# Wireless_Temp_Sensor.net
KiCad netlist of a schematic drawn in EAGLE
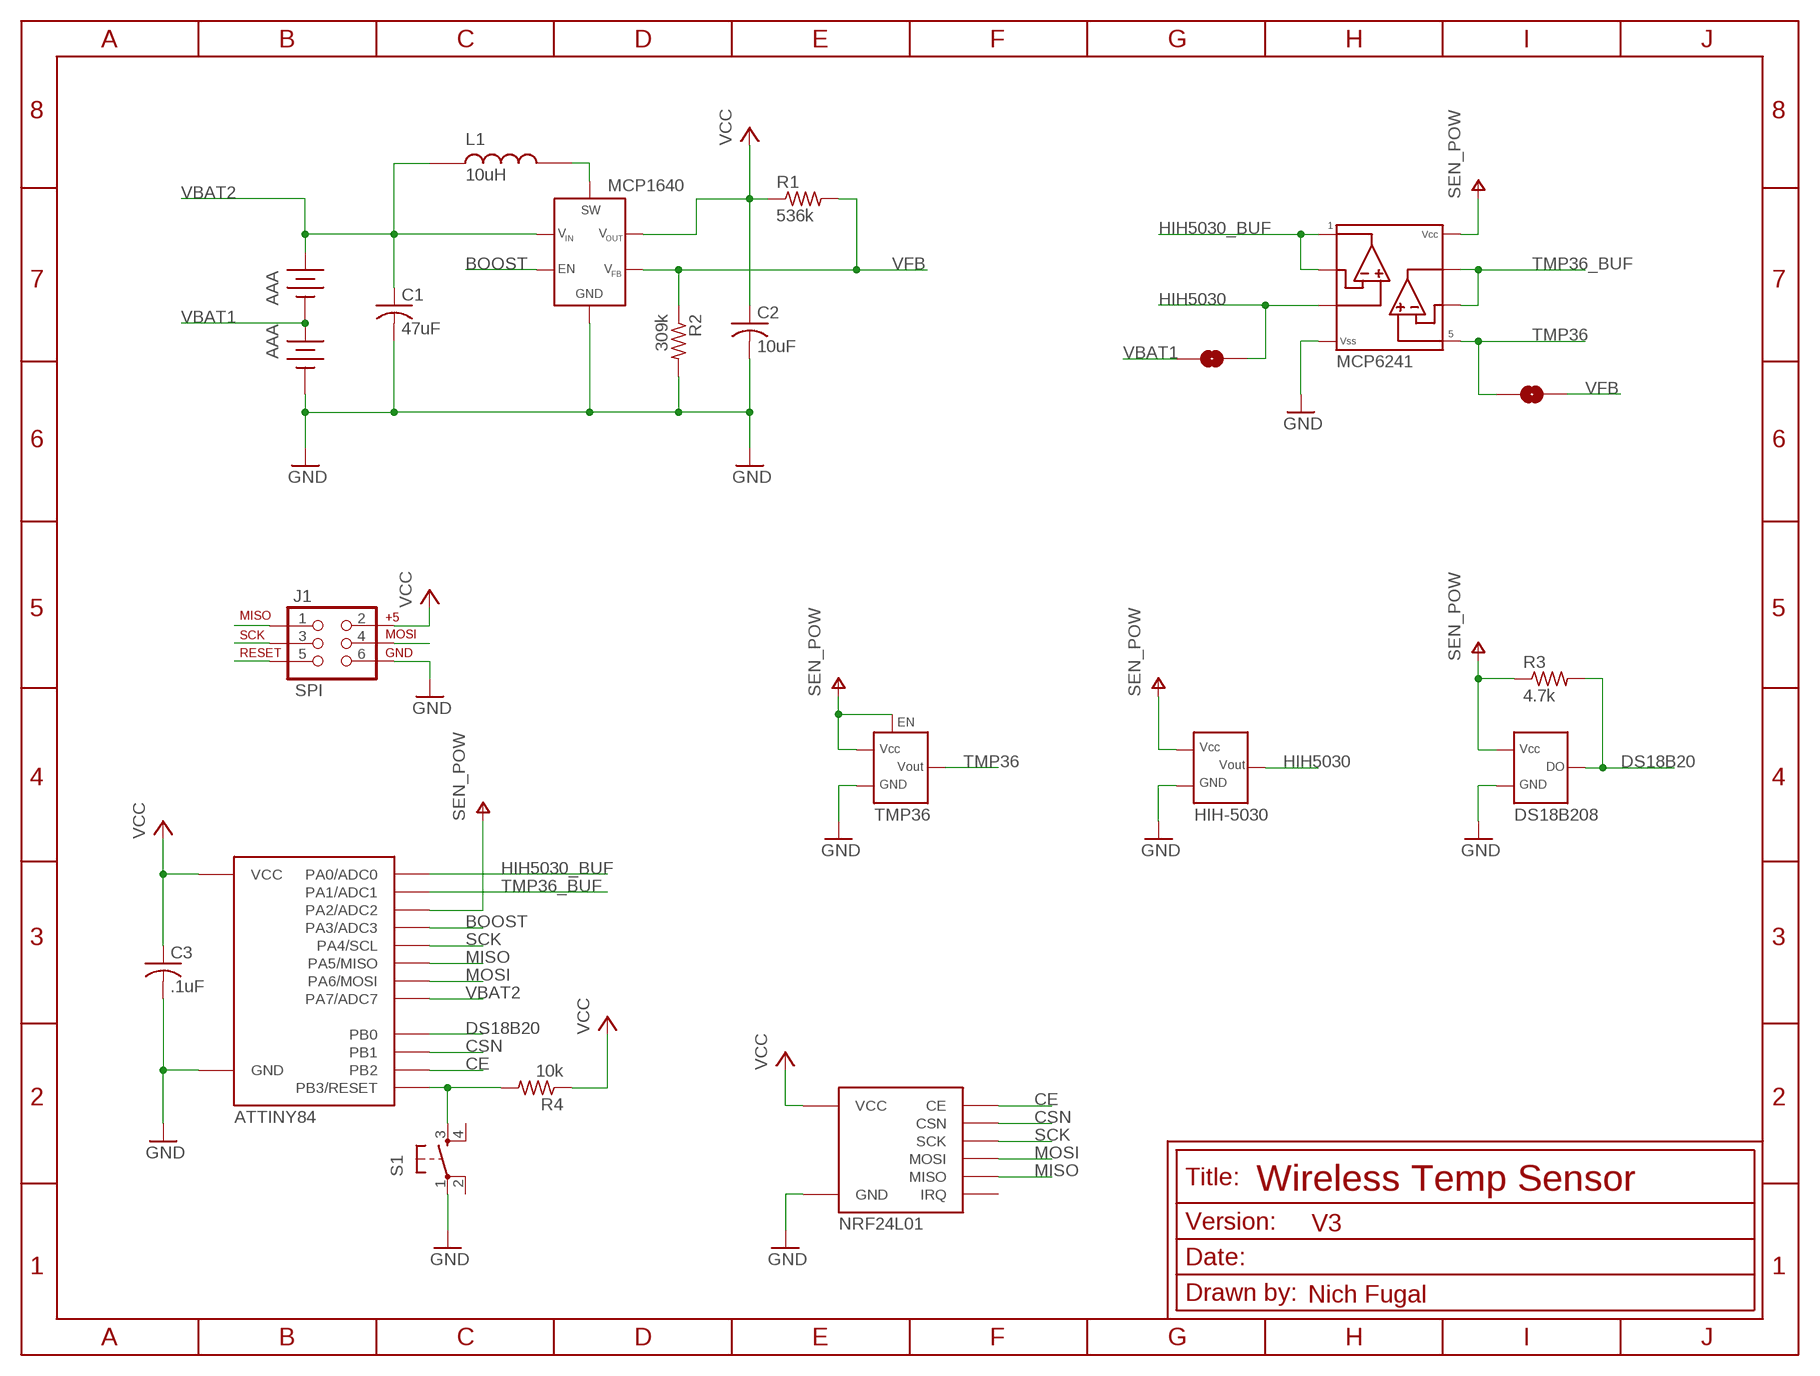
[diagram p0: schematic, sheet 1]

(export (version "E")
  (design (tool "Eeschema 10.0.6"))
  (components
    (comp (ref "C1")
      (value "47uF")
      (footprint "eagle-import:C0805")
      (libsource (lib "eagle-import") (part "C-USC0805"))
    )
    (comp (ref "C2")
      (value "10uF")
      (footprint "eagle-import:C0805")
      (libsource (lib "eagle-import") (part "C-USC0805"))
    )
    (comp (ref "C3")
      (value ".1uF")
      (footprint "eagle-import:C0805")
      (libsource (lib "eagle-import") (part "C-USC0805"))
    )
    (comp (ref "J1")
      (value "SPI")
      (footprint "eagle-import:2X3")
      (libsource (lib "eagle-import") (part "AVR_SPI_PRG_6PTH"))
    )
    (comp (ref "R1")
      (value "536k")
      (footprint "eagle-import:M0805")
      (libsource (lib "eagle-import") (part "R-US_M0805"))
    )
    (comp (ref "R2")
      (value "309k")
      (footprint "eagle-import:M0805")
      (libsource (lib "eagle-import") (part "R-US_M0805"))
    )
    (comp (ref "R3")
      (value "4.7k")
      (footprint "eagle-import:M0805")
      (libsource (lib "eagle-import") (part "R-US_M0805"))
    )
    (comp (ref "R4")
      (value "10k")
      (footprint "eagle-import:M0805")
      (libsource (lib "eagle-import") (part "R-US_M0805"))
    )
    (comp (ref "S1")
      (value "TAC_SWITCHPTH")
      (footprint "eagle-import:TACTILE-PTH")
      (libsource (lib "eagle-import") (part "TAC_SWITCHPTH"))
    )
    (comp (ref "SJ1")
      (value "SOLDERJUMPER-OLDNO")
      (footprint "eagle-import:SJ_2S-NO")
      (libsource (lib "eagle-import") (part "SOLDERJUMPER-OLDNO"))
    )
    (comp (ref "SJ2")
      (value "SOLDERJUMPER-OLDNO")
      (footprint "eagle-import:SJ_2S-NO")
      (libsource (lib "eagle-import") (part "SOLDERJUMPER-OLDNO"))
    )
    (comp (ref "U$1")
      (value "MCP1640")
      (footprint "eagle-import:SOT-23")
      (libsource (lib "eagle-import") (part "MCP1640SOT-23"))
    )
    (comp (ref "U$2")
      (value "10uH")
      (footprint "eagle-import:SD3114")
      (libsource (lib "eagle-import") (part "INDUCTORSD3114"))
    )
    (comp (ref "U$3")
      (value "AAA")
      (footprint "eagle-import:BK-82_MPD")
      (libsource (lib "eagle-import") (part "AAA"))
    )
    (comp (ref "U$4")
      (value "ATTINY84")
      (footprint "eagle-import:14-DIP")
      (libsource (lib "eagle-import") (part "ATTINY8414-DIP"))
    )
    (comp (ref "U$5")
      (value "NRF24L01")
      (footprint "eagle-import:NRF24L01")
      (libsource (lib "eagle-import") (part "NRF24L01"))
    )
    (comp (ref "U$6")
      (value "DS18B208")
      (footprint "eagle-import:8-MSOP")
      (libsource (lib "eagle-import") (part "DS18B208-MSOP"))
    )
    (comp (ref "U$7")
      (value "HIH-5030")
      (footprint "eagle-import:HIH-5030")
      (libsource (lib "eagle-import") (part "HIH-5030"))
    )
    (comp (ref "U$8")
      (value "AAA")
      (footprint "eagle-import:BK-82_MPD")
      (libsource (lib "eagle-import") (part "AAA"))
    )
    (comp (ref "U$9")
      (value "MCP6241")
      (footprint "eagle-import:8-SOIC")
      (libsource (lib "eagle-import") (part "MCP6241"))
    )
    (comp (ref "U1")
      (value "TMP36")
      (footprint "eagle-import:SOT-23-5")
      (libsource (lib "eagle-import") (part "TMP36"))
    )
  )
  (nets
    (net (code "1") (name "/BOOST") (class "Default")
      (node (ref "U$1") (pin "3") (pinfunction "EN_3") (pintype "bidirectional"))
      (node (ref "U$4") (pin "P$10") (pinfunction "PA3/ADC3_P$10") (pintype "bidirectional"))
    )
    (net (code "2") (name "/CE") (class "Default")
      (node (ref "U$4") (pin "P$5") (pinfunction "PB2_P$5") (pintype "bidirectional"))
      (node (ref "U$5") (pin "P$3") (pinfunction "CE_P$3") (pintype "bidirectional"))
    )
    (net (code "3") (name "/CSN") (class "Default")
      (node (ref "U$4") (pin "P$3") (pinfunction "PB1_P$3") (pintype "bidirectional"))
      (node (ref "U$5") (pin "P$4") (pinfunction "CSN_P$4") (pintype "bidirectional"))
    )
    (net (code "4") (name "/DS18B20") (class "Default")
      (node (ref "R3") (pin "2") (pinfunction "2_2") (pintype "passive"))
      (node (ref "U$4") (pin "P$2") (pinfunction "PB0_P$2") (pintype "bidirectional"))
      (node (ref "U$6") (pin "P$1") (pinfunction "DO_P$1") (pintype "bidirectional"))
    )
    (net (code "5") (name "/HIH5030") (class "Default")
      (node (ref "SJ1") (pin "1") (pinfunction "1_1") (pintype "passive"))
      (node (ref "U$7") (pin "OUT") (pinfunction "OUT_OUT") (pintype "bidirectional"))
      (node (ref "U$9") (pin "P$3") (pinfunction "P$3_P$3") (pintype "bidirectional"))
    )
    (net (code "6") (name "/HIH5030_BUF") (class "Default")
      (node (ref "U$4") (pin "P$13") (pinfunction "PA0/ADC0_P$13") (pintype "bidirectional"))
      (node (ref "U$9") (pin "P$1") (pinfunction "P$1_P$1") (pintype "bidirectional"))
      (node (ref "U$9") (pin "P$2") (pinfunction "P$2_P$2") (pintype "bidirectional"))
    )
    (net (code "7") (name "/MISO") (class "Default")
      (node (ref "J1") (pin "1") (pinfunction "1_1") (pintype "passive"))
      (node (ref "U$4") (pin "P$8") (pinfunction "PA5/MISO_P$8") (pintype "bidirectional"))
      (node (ref "U$5") (pin "P$7") (pinfunction "MISO_P$7") (pintype "bidirectional"))
    )
    (net (code "8") (name "/MOSI") (class "Default")
      (node (ref "J1") (pin "4") (pinfunction "4_4") (pintype "passive"))
      (node (ref "U$4") (pin "P$7") (pinfunction "PA6/MOSI_P$7") (pintype "bidirectional"))
      (node (ref "U$5") (pin "P$6") (pinfunction "MOSI_P$6") (pintype "bidirectional"))
    )
    (net (code "9") (name "/RESET") (class "Default")
      (node (ref "J1") (pin "5") (pinfunction "5_5") (pintype "passive"))
      (node (ref "R4") (pin "2") (pinfunction "2_2") (pintype "passive"))
      (node (ref "S1") (pin "3") (pinfunction "3_3") (pintype "passive"))
      (node (ref "U$4") (pin "P$4") (pinfunction "PB3/RESET_P$4") (pintype "bidirectional"))
    )
    (net (code "10") (name "/SCK") (class "Default")
      (node (ref "J1") (pin "3") (pinfunction "3_3") (pintype "passive"))
      (node (ref "U$4") (pin "P$9") (pinfunction "PA4/SCL_P$9") (pintype "bidirectional"))
      (node (ref "U$5") (pin "P$5") (pinfunction "SCK_P$5") (pintype "bidirectional"))
    )
    (net (code "11") (name "/TMP36") (class "Default")
      (node (ref "SJ2") (pin "1") (pinfunction "1_1") (pintype "passive"))
      (node (ref "U$9") (pin "P$5") (pinfunction "P$5_P$5") (pintype "bidirectional"))
      (node (ref "U1") (pin "1") (pinfunction "VOUT_1") (pintype "bidirectional"))
    )
    (net (code "12") (name "/TMP36_BUF") (class "Default")
      (node (ref "U$4") (pin "P$12") (pinfunction "PA1/ADC1_P$12") (pintype "bidirectional"))
      (node (ref "U$9") (pin "P$6") (pinfunction "P$6_P$6") (pintype "bidirectional"))
      (node (ref "U$9") (pin "P$7") (pinfunction "P$7_P$7") (pintype "bidirectional"))
    )
    (net (code "13") (name "/VBAT1") (class "Default")
      (node (ref "SJ1") (pin "2") (pinfunction "2_2") (pintype "passive"))
      (node (ref "U$3") (pin "P$3") (pinfunction "-_P$3") (pintype "bidirectional"))
      (node (ref "U$3") (pin "P$4") (pinfunction "-_P$4") (pintype "bidirectional"))
      (node (ref "U$8") (pin "P$1") (pinfunction "+_P$1") (pintype "bidirectional"))
      (node (ref "U$8") (pin "P$2") (pinfunction "+_P$2") (pintype "bidirectional"))
    )
    (net (code "14") (name "/VBAT2") (class "Default")
      (node (ref "C1") (pin "1") (pinfunction "1_1") (pintype "passive"))
      (node (ref "U$1") (pin "6") (pinfunction "VIN_6") (pintype "bidirectional"))
      (node (ref "U$2") (pin "P$1") (pinfunction "P$1_P$1") (pintype "bidirectional"))
      (node (ref "U$3") (pin "P$1") (pinfunction "+_P$1") (pintype "bidirectional"))
      (node (ref "U$3") (pin "P$2") (pinfunction "+_P$2") (pintype "bidirectional"))
      (node (ref "U$4") (pin "P$6") (pinfunction "PA7/ADC7_P$6") (pintype "bidirectional"))
    )
    (net (code "15") (name "/VFB") (class "Default")
      (node (ref "R1") (pin "2") (pinfunction "2_2") (pintype "passive"))
      (node (ref "R2") (pin "1") (pinfunction "1_1") (pintype "passive"))
      (node (ref "SJ2") (pin "2") (pinfunction "2_2") (pintype "passive"))
      (node (ref "U$1") (pin "4") (pinfunction "VFB_4") (pintype "bidirectional"))
    )
    (net (code "16") (name "GND") (class "Default")
      (node (ref "C1") (pin "2") (pinfunction "2_2") (pintype "passive"))
      (node (ref "C2") (pin "2") (pinfunction "2_2") (pintype "passive"))
      (node (ref "C3") (pin "2") (pinfunction "2_2") (pintype "passive"))
      (node (ref "J1") (pin "6") (pinfunction "6_6") (pintype "passive"))
      (node (ref "R2") (pin "2") (pinfunction "2_2") (pintype "passive"))
      (node (ref "S1") (pin "1") (pinfunction "1_1") (pintype "passive"))
      (node (ref "U$1") (pin "2") (pinfunction "GND_2") (pintype "bidirectional"))
      (node (ref "U$4") (pin "P$14") (pinfunction "GND_P$14") (pintype "bidirectional"))
      (node (ref "U$5") (pin "P$1") (pinfunction "GND_P$1") (pintype "bidirectional"))
      (node (ref "U$6") (pin "P$4") (pinfunction "GND_P$4") (pintype "bidirectional"))
      (node (ref "U$7") (pin "GND") (pinfunction "GND_GND") (pintype "bidirectional"))
      (node (ref "U$8") (pin "P$3") (pinfunction "-_P$3") (pintype "bidirectional"))
      (node (ref "U$8") (pin "P$4") (pinfunction "-_P$4") (pintype "bidirectional"))
      (node (ref "U$9") (pin "P$4") (pinfunction "P$4_P$4") (pintype "bidirectional"))
      (node (ref "U1") (pin "5") (pinfunction "GND_5") (pintype "bidirectional"))
    )
    (net (code "17") (name "Net-(U$1-SW)") (class "Default")
      (node (ref "U$1") (pin "1") (pinfunction "SW_1") (pintype "bidirectional"))
      (node (ref "U$2") (pin "P$2") (pinfunction "P$2_P$2") (pintype "bidirectional"))
    )
    (net (code "18") (name "SEN_POW") (class "Default")
      (node (ref "R3") (pin "1") (pinfunction "1_1") (pintype "passive"))
      (node (ref "U$4") (pin "P$11") (pinfunction "PA2/ADC2_P$11") (pintype "bidirectional"))
      (node (ref "U$6") (pin "P$8") (pinfunction "VCC_P$8") (pintype "bidirectional"))
      (node (ref "U$7") (pin "VCC") (pinfunction "VCC_VCC") (pintype "bidirectional"))
      (node (ref "U$9") (pin "P$8") (pinfunction "P$8_P$8") (pintype "bidirectional"))
      (node (ref "U1") (pin "2") (pinfunction "VCC_2") (pintype "bidirectional"))
      (node (ref "U1") (pin "4") (pinfunction "EN_4") (pintype "bidirectional"))
    )
    (net (code "19") (name "VCC") (class "Default")
      (node (ref "C2") (pin "1") (pinfunction "1_1") (pintype "passive"))
      (node (ref "C3") (pin "1") (pinfunction "1_1") (pintype "passive"))
      (node (ref "J1") (pin "2") (pinfunction "2_2") (pintype "passive"))
      (node (ref "R1") (pin "1") (pinfunction "1_1") (pintype "passive"))
      (node (ref "R4") (pin "1") (pinfunction "1_1") (pintype "passive"))
      (node (ref "U$1") (pin "5") (pinfunction "VOUT_5") (pintype "bidirectional"))
      (node (ref "U$4") (pin "P$1") (pinfunction "VCC_P$1") (pintype "bidirectional"))
      (node (ref "U$5") (pin "P$2") (pinfunction "VCC_P$2") (pintype "bidirectional"))
    )
    (net (code "20") (name "unconnected-(S1-Pad2)") (class "Default")
      (node (ref "S1") (pin "2") (pinfunction "2_2") (pintype "passive"))
    )
    (net (code "21") (name "unconnected-(S1-Pad4)") (class "Default")
      (node (ref "S1") (pin "4") (pinfunction "4_4") (pintype "passive"))
    )
    (net (code "22") (name "unconnected-(U$5-IRQ-PadP$8)") (class "Default")
      (node (ref "U$5") (pin "P$8") (pinfunction "IRQ_P$8") (pintype "bidirectional"))
    )
  )
)
